# TLC4LEDShield.net
KiCad netlist of a schematic drawn in EAGLE
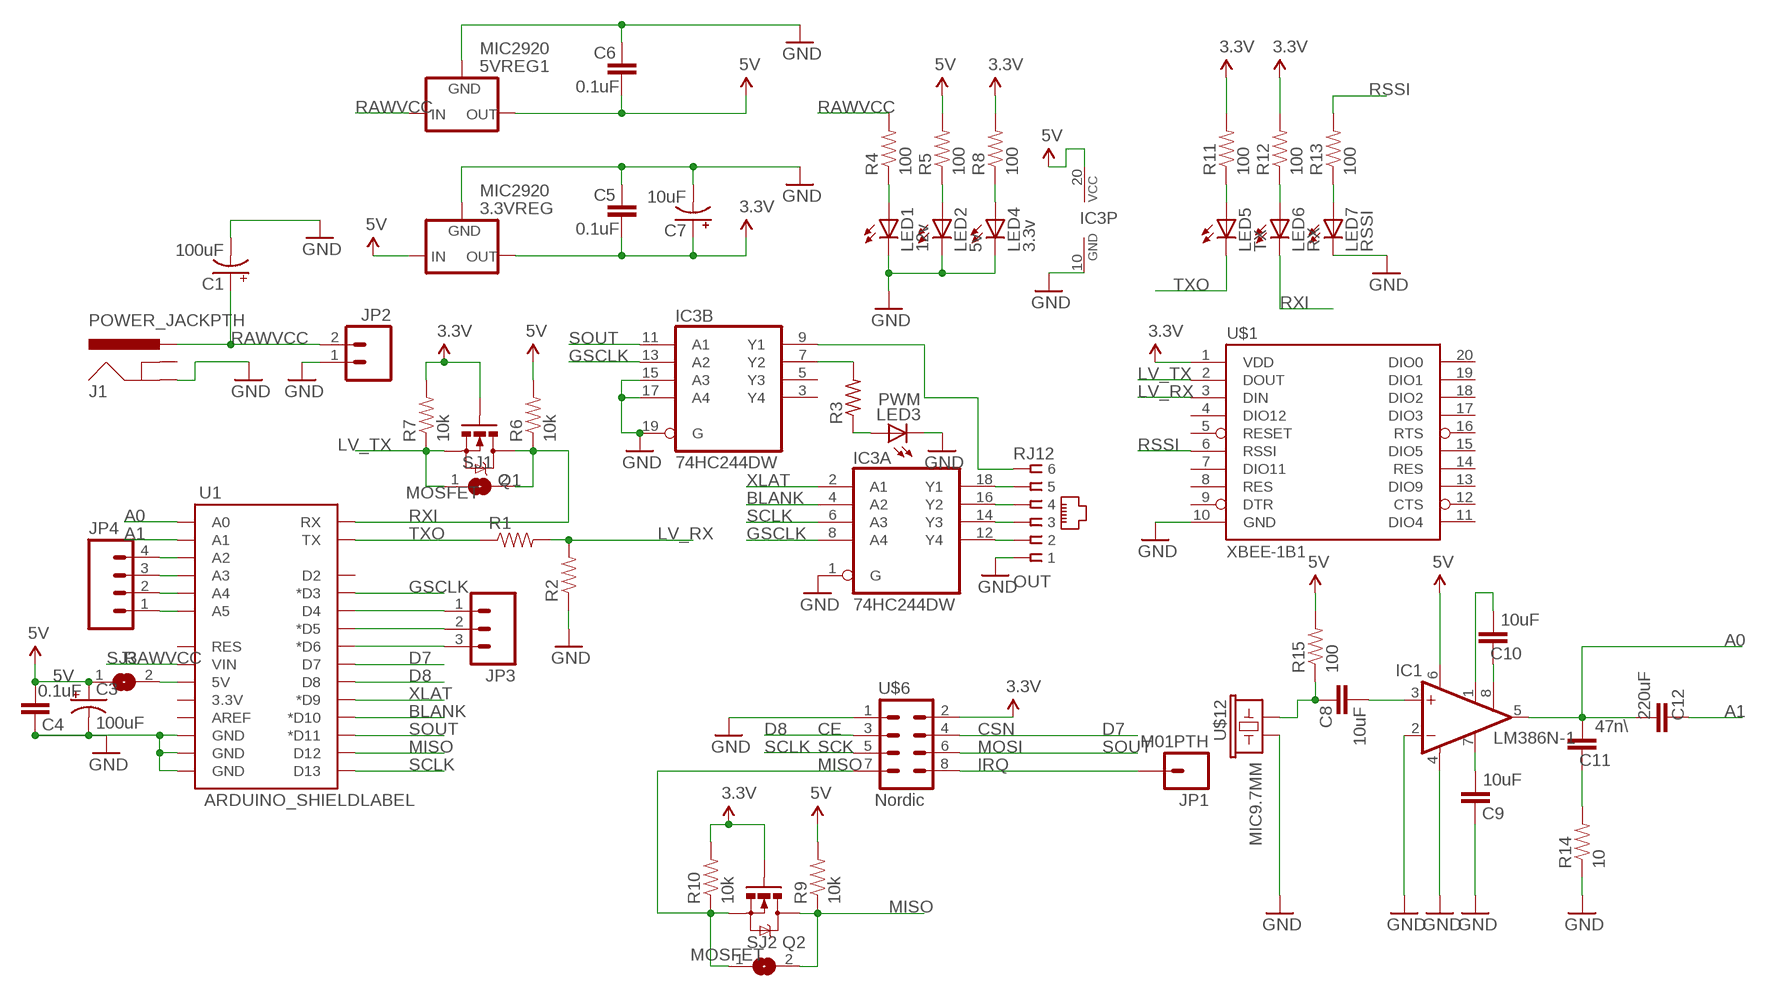
[diagram p0: schematic, sheet 1]

(export (version "E")
  (design (tool "Eeschema 10.0.6"))
  (components
    (comp (ref "3.3VREG")
      (value "MIC2920")
      (footprint "eagle-import:SOT223")
      (libsource (lib "eagle-import") (part "V_REG_MIC2920"))
    )
    (comp (ref "5VREG1")
      (value "MIC2920")
      (footprint "eagle-import:SOT223")
      (libsource (lib "eagle-import") (part "V_REG_MIC2920"))
    )
    (comp (ref "C1")
      (value "100uF")
      (footprint "eagle-import:PANASONIC_D")
      (libsource (lib "eagle-import") (part "CAP_POLD"))
    )
    (comp (ref "C3")
      (value "100uF")
      (footprint "eagle-import:PANASONIC_D")
      (libsource (lib "eagle-import") (part "CAP_POLD"))
    )
    (comp (ref "C4")
      (value "0.1uF")
      (footprint "eagle-import:0805")
      (libsource (lib "eagle-import") (part "CAP0805"))
    )
    (comp (ref "C5")
      (value "0.1uF")
      (footprint "eagle-import:0805")
      (libsource (lib "eagle-import") (part "CAP0805"))
    )
    (comp (ref "C6")
      (value "0.1uF")
      (footprint "eagle-import:0805")
      (libsource (lib "eagle-import") (part "CAP0805"))
    )
    (comp (ref "C7")
      (value "10uF")
      (footprint "eagle-import:EIA3216")
      (libsource (lib "eagle-import") (part "CAP_POL1206"))
    )
    (comp (ref "C8")
      (value "10uF")
      (footprint "eagle-import:0805")
      (libsource (lib "eagle-import") (part "CAP0805"))
    )
    (comp (ref "C9")
      (value "10uF")
      (footprint "eagle-import:0805")
      (libsource (lib "eagle-import") (part "CAP0805"))
    )
    (comp (ref "C10")
      (value "10uF")
      (footprint "eagle-import:0805")
      (libsource (lib "eagle-import") (part "CAP0805"))
    )
    (comp (ref "C11")
      (value "47n\\")
      (footprint "eagle-import:0805")
      (libsource (lib "eagle-import") (part "CAP0805"))
    )
    (comp (ref "C12")
      (value "220uF")
      (footprint "eagle-import:0805")
      (libsource (lib "eagle-import") (part "CAP0805"))
    )
    (comp (ref "IC1")
      (value "LM386N-1")
      (footprint "eagle-import:DIL08")
      (libsource (lib "eagle-import") (part "LM386?-N1"))
    )
    (comp (ref "IC3")
      (value "74HC244DW")
      (footprint "eagle-import:SO20W")
      (libsource (lib "eagle-import") (part "74244DWHC"))
    )
    (comp (ref "J1")
      (value "POWER_JACKPTH")
      (footprint "eagle-import:POWER_JACK_PTH")
      (libsource (lib "eagle-import") (part "POWER_JACKPTH"))
    )
    (comp (ref "JP1")
      (value "M01PTH")
      (footprint "eagle-import:1X01")
      (libsource (lib "eagle-import") (part "M01PTH"))
    )
    (comp (ref "JP2")
      (value "M025MM")
      (footprint "eagle-import:SCREWTERMINAL-5MM-2")
      (libsource (lib "eagle-import") (part "M025MM"))
    )
    (comp (ref "JP3")
      (value "M03PTH")
      (footprint "eagle-import:1X03")
      (libsource (lib "eagle-import") (part "M03PTH"))
    )
    (comp (ref "JP4")
      (value "M04PTH")
      (footprint "eagle-import:1X04")
      (libsource (lib "eagle-import") (part "M04PTH"))
    )
    (comp (ref "LED1")
      (value "12v")
      (footprint "eagle-import:CHIPLED_0805")
      (libsource (lib "eagle-import") (part "LEDCHIPLED_0805"))
    )
    (comp (ref "LED2")
      (value "5v")
      (footprint "eagle-import:CHIPLED_0805")
      (libsource (lib "eagle-import") (part "LEDCHIPLED_0805"))
    )
    (comp (ref "LED3")
      (value "PWM")
      (footprint "eagle-import:CHIPLED_0805")
      (libsource (lib "eagle-import") (part "LEDCHIPLED_0805"))
    )
    (comp (ref "LED4")
      (value "3.3v")
      (footprint "eagle-import:CHIPLED_0805")
      (libsource (lib "eagle-import") (part "LEDCHIPLED_0805"))
    )
    (comp (ref "LED5")
      (value "TX")
      (footprint "eagle-import:CHIPLED_0805")
      (libsource (lib "eagle-import") (part "LEDCHIPLED_0805"))
    )
    (comp (ref "LED6")
      (value "RX")
      (footprint "eagle-import:CHIPLED_0805")
      (libsource (lib "eagle-import") (part "LEDCHIPLED_0805"))
    )
    (comp (ref "LED7")
      (value "RSSI")
      (footprint "eagle-import:CHIPLED_0805")
      (libsource (lib "eagle-import") (part "LEDCHIPLED_0805"))
    )
    (comp (ref "OUT")
      (value "RJ12")
      (footprint "eagle-import:RJ11-NO_SHIELD")
      (fields
        (field (name "MF") "TYCO ELECTRONICS")
        (field (name "MPN") "RJ11-6L-B")
        (field (name "MF_1") "TYCO ELECTRONICS")
        (field (name "MPN_1") "RJ11-6L-B")
        (field (name "OC_FARNELL") "unknown")
        (field (name "OC_NEWARK") "52K3613")
      )
      (libsource (lib "eagle-import") (part "RJ11-6L-B"))
    )
    (comp (ref "Q1")
      (value "MOSFET")
      (footprint "eagle-import:SOT23-3")
      (libsource (lib "eagle-import") (part "MOSFET-NCHANNELSMD"))
    )
    (comp (ref "Q2")
      (value "MOSFET")
      (footprint "eagle-import:SOT23-3")
      (libsource (lib "eagle-import") (part "MOSFET-NCHANNELSMD"))
    )
    (comp (ref "R1")
      (value "RESISTOR0805-RES")
      (footprint "eagle-import:0805")
      (libsource (lib "eagle-import") (part "RESISTOR0805-RES"))
    )
    (comp (ref "R2")
      (value "RESISTOR0805-RES")
      (footprint "eagle-import:0805")
      (libsource (lib "eagle-import") (part "RESISTOR0805-RES"))
    )
    (comp (ref "R3")
      (value "R-US_R0805")
      (footprint "eagle-import:R0805")
      (libsource (lib "eagle-import") (part "R-US_R0805"))
    )
    (comp (ref "R4")
      (value "100")
      (footprint "eagle-import:0805")
      (libsource (lib "eagle-import") (part "RESISTOR0805-RES"))
    )
    (comp (ref "R5")
      (value "100")
      (footprint "eagle-import:0805")
      (libsource (lib "eagle-import") (part "RESISTOR0805-RES"))
    )
    (comp (ref "R6")
      (value "10k")
      (footprint "eagle-import:0805")
      (libsource (lib "eagle-import") (part "RESISTOR0805-RES"))
    )
    (comp (ref "R7")
      (value "10k")
      (footprint "eagle-import:0805")
      (libsource (lib "eagle-import") (part "RESISTOR0805-RES"))
    )
    (comp (ref "R8")
      (value "100")
      (footprint "eagle-import:0805")
      (libsource (lib "eagle-import") (part "RESISTOR0805-RES"))
    )
    (comp (ref "R9")
      (value "10k")
      (footprint "eagle-import:0805")
      (libsource (lib "eagle-import") (part "RESISTOR0805-RES"))
    )
    (comp (ref "R10")
      (value "10k")
      (footprint "eagle-import:0805")
      (libsource (lib "eagle-import") (part "RESISTOR0805-RES"))
    )
    (comp (ref "R11")
      (value "100")
      (footprint "eagle-import:0805")
      (libsource (lib "eagle-import") (part "RESISTOR0805-RES"))
    )
    (comp (ref "R12")
      (value "100")
      (footprint "eagle-import:0805")
      (libsource (lib "eagle-import") (part "RESISTOR0805-RES"))
    )
    (comp (ref "R13")
      (value "100")
      (footprint "eagle-import:0805")
      (libsource (lib "eagle-import") (part "RESISTOR0805-RES"))
    )
    (comp (ref "R14")
      (value "10")
      (footprint "eagle-import:0805")
      (libsource (lib "eagle-import") (part "RESISTOR0805-RES"))
    )
    (comp (ref "R15")
      (value "100")
      (footprint "eagle-import:0805")
      (libsource (lib "eagle-import") (part "RESISTOR0805-RES"))
    )
    (comp (ref "SJ1") (value "SJ") (footprint "eagle-import:SJ") (libsource (lib "eagle-import") (part "SJ")))
    (comp (ref "SJ2") (value "SJ") (footprint "eagle-import:SJ") (libsource (lib "eagle-import") (part "SJ")))
    (comp (ref "SJ3") (value "SJ") (footprint "eagle-import:SJ") (libsource (lib "eagle-import") (part "SJ")))
    (comp (ref "U$1")
      (value "XBEE-1B1")
      (footprint "eagle-import:XBEE-1")
      (libsource (lib "eagle-import") (part "XBEE-1B1"))
    )
    (comp (ref "U$6")
      (value "Nordic")
      (footprint "eagle-import:2X4")
      (libsource (lib "eagle-import") (part "M04X2"))
    )
    (comp (ref "U$12")
      (value "MIC9.7MM")
      (footprint "eagle-import:MIC-9.7MM")
      (libsource (lib "eagle-import") (part "MIC9.7MM"))
    )
    (comp (ref "U1")
      (value "ARDUINO_SHIELDLABEL")
      (footprint "eagle-import:DUEMILANOVE_SHIELD")
      (libsource (lib "eagle-import") (part "ARDUINO_SHIELDLABEL"))
    )
  )
  (nets
    (net (code "1") (name "/A0") (class "Default")
      (node (ref "C11") (pin "1") (pinfunction "1_1") (pintype "passive"))
      (node (ref "C12") (pin "1") (pinfunction "1_1") (pintype "passive"))
      (node (ref "IC1") (pin "5") (pinfunction "OUT_5") (pintype "output"))
      (node (ref "U1") (pin "A0") (pinfunction "A0_A0") (pintype "bidirectional"))
    )
    (net (code "2") (name "/A1") (class "Default")
      (node (ref "C12") (pin "2") (pinfunction "2_2") (pintype "passive"))
      (node (ref "U1") (pin "A1") (pinfunction "A1_A1") (pintype "bidirectional"))
    )
    (net (code "3") (name "/BLANK") (class "Default")
      (node (ref "IC3") (pin "4") (pinfunction "A2_4") (pintype "input"))
      (node (ref "U1") (pin "D10") (pinfunction "*D10_D10") (pintype "bidirectional"))
    )
    (net (code "4") (name "/D7") (class "Default")
      (node (ref "U$6") (pin "4") (pinfunction "4_4") (pintype "passive"))
      (node (ref "U1") (pin "D7") (pinfunction "D7_D7") (pintype "bidirectional"))
    )
    (net (code "5") (name "/D8") (class "Default")
      (node (ref "U$6") (pin "3") (pinfunction "3_3") (pintype "passive"))
      (node (ref "U1") (pin "D8") (pinfunction "D8_D8") (pintype "bidirectional"))
    )
    (net (code "6") (name "/GSCLK") (class "Default")
      (node (ref "IC3") (pin "13") (pinfunction "A2_13") (pintype "input"))
      (node (ref "IC3") (pin "8") (pinfunction "A4_8") (pintype "input"))
      (node (ref "U1") (pin "D3") (pinfunction "*D3_D3") (pintype "bidirectional"))
    )
    (net (code "7") (name "/LV_RX") (class "Default")
      (node (ref "R1") (pin "2") (pinfunction "2_2") (pintype "passive"))
      (node (ref "R2") (pin "2") (pinfunction "2_2") (pintype "passive"))
      (node (ref "U$1") (pin "3") (pinfunction "DIN_3") (pintype "input"))
    )
    (net (code "8") (name "/LV_TX") (class "Default")
      (node (ref "Q1") (pin "2") (pinfunction "S_2") (pintype "passive"))
      (node (ref "R7") (pin "1") (pinfunction "1_1") (pintype "passive"))
      (node (ref "SJ1") (pin "1") (pinfunction "1_1") (pintype "passive"))
      (node (ref "U$1") (pin "2") (pinfunction "DOUT_2") (pintype "output"))
    )
    (net (code "9") (name "/MISO") (class "Default")
      (node (ref "Q2") (pin "3") (pinfunction "D_3") (pintype "passive"))
      (node (ref "R9") (pin "1") (pinfunction "1_1") (pintype "passive"))
      (node (ref "SJ2") (pin "2") (pinfunction "2_2") (pintype "passive"))
      (node (ref "U1") (pin "D12") (pinfunction "D12_D12") (pintype "bidirectional"))
    )
    (net (code "10") (name "/RAWVCC") (class "Default")
      (node (ref "5VREG1") (pin "1") (pinfunction "IN_1") (pintype "input"))
      (node (ref "C1") (pin "+") (pinfunction "+_+") (pintype "passive"))
      (node (ref "J1") (pin "PWR") (pinfunction "PWR_PWR") (pintype "bidirectional"))
      (node (ref "JP2") (pin "2") (pinfunction "2_2") (pintype "passive"))
      (node (ref "R4") (pin "2") (pinfunction "2_2") (pintype "passive"))
      (node (ref "U1") (pin "VIN") (pinfunction "VIN_VIN") (pintype "bidirectional"))
    )
    (net (code "11") (name "/RSSI") (class "Default")
      (node (ref "R13") (pin "2") (pinfunction "2_2") (pintype "passive"))
      (node (ref "U$1") (pin "6") (pinfunction "RSSI_6") (pintype "bidirectional"))
    )
    (net (code "12") (name "/RXI") (class "Default")
      (node (ref "LED6") (pin "C") (pinfunction "C_C") (pintype "passive"))
      (node (ref "Q1") (pin "3") (pinfunction "D_3") (pintype "passive"))
      (node (ref "R6") (pin "1") (pinfunction "1_1") (pintype "passive"))
      (node (ref "SJ1") (pin "2") (pinfunction "2_2") (pintype "passive"))
      (node (ref "U1") (pin "RX") (pinfunction "RX_RX") (pintype "bidirectional"))
    )
    (net (code "13") (name "/SCLK") (class "Default")
      (node (ref "IC3") (pin "6") (pinfunction "A3_6") (pintype "input"))
      (node (ref "U$6") (pin "5") (pinfunction "5_5") (pintype "passive"))
      (node (ref "U1") (pin "D13") (pinfunction "D13_D13") (pintype "bidirectional"))
    )
    (net (code "14") (name "/SOUT") (class "Default")
      (node (ref "IC3") (pin "11") (pinfunction "A1_11") (pintype "input"))
      (node (ref "U$6") (pin "6") (pinfunction "6_6") (pintype "passive"))
      (node (ref "U1") (pin "D11") (pinfunction "*D11_D11") (pintype "bidirectional"))
    )
    (net (code "15") (name "/TXO") (class "Default")
      (node (ref "LED5") (pin "C") (pinfunction "C_C") (pintype "passive"))
      (node (ref "R1") (pin "1") (pinfunction "1_1") (pintype "passive"))
      (node (ref "U1") (pin "TX") (pinfunction "TX_TX") (pintype "bidirectional"))
    )
    (net (code "16") (name "/XLAT") (class "Default")
      (node (ref "IC3") (pin "2") (pinfunction "A1_2") (pintype "input"))
      (node (ref "U1") (pin "D9") (pinfunction "*D9_D9") (pintype "bidirectional"))
    )
    (net (code "17") (name "3.3V") (class "Default")
      (node (ref "3.3VREG") (pin "3") (pinfunction "OUT_3") (pintype "output"))
      (node (ref "C5") (pin "1") (pinfunction "1_1") (pintype "passive"))
      (node (ref "C7") (pin "A") (pinfunction "+_A") (pintype "passive"))
      (node (ref "Q1") (pin "1") (pinfunction "G_1") (pintype "passive"))
      (node (ref "Q2") (pin "1") (pinfunction "G_1") (pintype "passive"))
      (node (ref "R10") (pin "2") (pinfunction "2_2") (pintype "passive"))
      (node (ref "R11") (pin "2") (pinfunction "2_2") (pintype "passive"))
      (node (ref "R12") (pin "2") (pinfunction "2_2") (pintype "passive"))
      (node (ref "R7") (pin "2") (pinfunction "2_2") (pintype "passive"))
      (node (ref "R8") (pin "2") (pinfunction "2_2") (pintype "passive"))
      (node (ref "U$1") (pin "1") (pinfunction "VDD_1") (pintype "power_in"))
      (node (ref "U$6") (pin "2") (pinfunction "2_2") (pintype "passive"))
    )
    (net (code "18") (name "5V") (class "Default")
      (node (ref "3.3VREG") (pin "1") (pinfunction "IN_1") (pintype "input"))
      (node (ref "5VREG1") (pin "3") (pinfunction "OUT_3") (pintype "output"))
      (node (ref "C3") (pin "+") (pinfunction "+_+") (pintype "passive"))
      (node (ref "C4") (pin "1") (pinfunction "1_1") (pintype "passive"))
      (node (ref "C6") (pin "1") (pinfunction "1_1") (pintype "passive"))
      (node (ref "IC1") (pin "6") (pinfunction "VS_6") (pintype "power_in"))
      (node (ref "IC3") (pin "20") (pinfunction "VCC_20") (pintype "power_in"))
      (node (ref "R15") (pin "2") (pinfunction "2_2") (pintype "passive"))
      (node (ref "R5") (pin "2") (pinfunction "2_2") (pintype "passive"))
      (node (ref "R6") (pin "2") (pinfunction "2_2") (pintype "passive"))
      (node (ref "R9") (pin "2") (pinfunction "2_2") (pintype "passive"))
      (node (ref "SJ3") (pin "1") (pinfunction "1_1") (pintype "passive"))
    )
    (net (code "19") (name "GND") (class "Default")
      (node (ref "3.3VREG") (pin "2") (pinfunction "GND_2") (pintype "input"))
      (node (ref "5VREG1") (pin "2") (pinfunction "GND_2") (pintype "input"))
      (node (ref "C1") (pin "-") (pinfunction "-_-") (pintype "passive"))
      (node (ref "C3") (pin "-") (pinfunction "-_-") (pintype "passive"))
      (node (ref "C4") (pin "2") (pinfunction "2_2") (pintype "passive"))
      (node (ref "C5") (pin "2") (pinfunction "2_2") (pintype "passive"))
      (node (ref "C6") (pin "2") (pinfunction "2_2") (pintype "passive"))
      (node (ref "C7") (pin "C") (pinfunction "-_C") (pintype "passive"))
      (node (ref "C9") (pin "2") (pinfunction "2_2") (pintype "passive"))
      (node (ref "IC1") (pin "2") (pinfunction "-IN_2") (pintype "input"))
      (node (ref "IC1") (pin "4") (pinfunction "GND_4") (pintype "power_in"))
      (node (ref "IC3") (pin "1") (pinfunction "G_1") (pintype "input"))
      (node (ref "IC3") (pin "10") (pinfunction "GND_10") (pintype "power_in"))
      (node (ref "IC3") (pin "15") (pinfunction "A3_15") (pintype "input"))
      (node (ref "IC3") (pin "17") (pinfunction "A4_17") (pintype "input"))
      (node (ref "IC3") (pin "19") (pinfunction "G_19") (pintype "input"))
      (node (ref "J1") (pin "GND") (pinfunction "GND_GND") (pintype "bidirectional"))
      (node (ref "JP2") (pin "1") (pinfunction "1_1") (pintype "passive"))
      (node (ref "LED1") (pin "C") (pinfunction "C_C") (pintype "passive"))
      (node (ref "LED2") (pin "C") (pinfunction "C_C") (pintype "passive"))
      (node (ref "LED3") (pin "C") (pinfunction "C_C") (pintype "passive"))
      (node (ref "LED4") (pin "C") (pinfunction "C_C") (pintype "passive"))
      (node (ref "LED7") (pin "C") (pinfunction "C_C") (pintype "passive"))
      (node (ref "OUT") (pin "1") (pinfunction "1_1") (pintype "passive"))
      (node (ref "R14") (pin "1") (pinfunction "1_1") (pintype "passive"))
      (node (ref "R2") (pin "1") (pinfunction "1_1") (pintype "passive"))
      (node (ref "U$1") (pin "10") (pinfunction "GND_10") (pintype "power_in"))
      (node (ref "U$12") (pin "2") (pinfunction "2_2") (pintype "passive"))
      (node (ref "U$6") (pin "1") (pinfunction "1_1") (pintype "passive"))
      (node (ref "U1") (pin "GND@0") (pinfunction "GND_GND@0") (pintype "bidirectional"))
      (node (ref "U1") (pin "GND@1") (pinfunction "GND_GND@1") (pintype "bidirectional"))
      (node (ref "U1") (pin "GND@2") (pinfunction "GND_GND@2") (pintype "bidirectional"))
    )
    (net (code "20") (name "Net-(C8-Pad2)") (class "Default")
      (node (ref "C8") (pin "2") (pinfunction "2_2") (pintype "passive"))
      (node (ref "R15") (pin "1") (pinfunction "1_1") (pintype "passive"))
      (node (ref "U$12") (pin "1") (pinfunction "1_1") (pintype "passive"))
    )
    (net (code "21") (name "Net-(C10-Pad1)") (class "Default")
      (node (ref "C10") (pin "1") (pinfunction "1_1") (pintype "passive"))
      (node (ref "IC1") (pin "1") (pinfunction "GAIN_1") (pintype "passive"))
    )
    (net (code "22") (name "Net-(C10-Pad2)") (class "Default")
      (node (ref "C10") (pin "2") (pinfunction "2_2") (pintype "passive"))
      (node (ref "IC1") (pin "8") (pinfunction "GAIN_8") (pintype "passive"))
    )
    (net (code "23") (name "Net-(C11-Pad2)") (class "Default")
      (node (ref "C11") (pin "2") (pinfunction "2_2") (pintype "passive"))
      (node (ref "R14") (pin "2") (pinfunction "2_2") (pintype "passive"))
    )
    (net (code "24") (name "Net-(IC1-+IN)") (class "Default")
      (node (ref "C8") (pin "1") (pinfunction "1_1") (pintype "passive"))
      (node (ref "IC1") (pin "3") (pinfunction "+IN_3") (pintype "input"))
    )
    (net (code "25") (name "Net-(IC1-BYPASS)") (class "Default")
      (node (ref "C9") (pin "1") (pinfunction "1_1") (pintype "passive"))
      (node (ref "IC1") (pin "7") (pinfunction "BYPASS_7") (pintype "passive"))
    )
    (net (code "26") (name "Net-(IC3A-Y1)") (class "Default")
      (node (ref "IC3") (pin "18") (pinfunction "Y1_18") (pintype "tri_state"))
      (node (ref "OUT") (pin "5") (pinfunction "5_5") (pintype "passive"))
    )
    (net (code "27") (name "Net-(IC3A-Y2)") (class "Default")
      (node (ref "IC3") (pin "16") (pinfunction "Y2_16") (pintype "tri_state"))
      (node (ref "OUT") (pin "4") (pinfunction "4_4") (pintype "passive"))
    )
    (net (code "28") (name "Net-(IC3A-Y3)") (class "Default")
      (node (ref "IC3") (pin "14") (pinfunction "Y3_14") (pintype "tri_state"))
      (node (ref "OUT") (pin "3") (pinfunction "3_3") (pintype "passive"))
    )
    (net (code "29") (name "Net-(IC3A-Y4)") (class "Default")
      (node (ref "IC3") (pin "12") (pinfunction "Y4_12") (pintype "tri_state"))
      (node (ref "OUT") (pin "2") (pinfunction "2_2") (pintype "passive"))
    )
    (net (code "30") (name "Net-(IC3B-Y1)") (class "Default")
      (node (ref "IC3") (pin "9") (pinfunction "Y1_9") (pintype "tri_state"))
      (node (ref "OUT") (pin "6") (pinfunction "6_6") (pintype "passive"))
    )
    (net (code "31") (name "Net-(IC3B-Y2)") (class "Default")
      (node (ref "IC3") (pin "7") (pinfunction "Y2_7") (pintype "tri_state"))
      (node (ref "R3") (pin "2") (pinfunction "2_2") (pintype "passive"))
    )
    (net (code "32") (name "Net-(JP1-Pad1)") (class "Default")
      (node (ref "JP1") (pin "1") (pinfunction "1_1") (pintype "passive"))
      (node (ref "U$6") (pin "8") (pinfunction "8_8") (pintype "passive"))
    )
    (net (code "33") (name "Net-(JP3-Pad1)") (class "Default")
      (node (ref "JP3") (pin "1") (pinfunction "1_1") (pintype "passive"))
      (node (ref "U1") (pin "D4") (pinfunction "D4_D4") (pintype "bidirectional"))
    )
    (net (code "34") (name "Net-(JP4-Pad1)") (class "Default")
      (node (ref "JP4") (pin "1") (pinfunction "1_1") (pintype "passive"))
      (node (ref "U1") (pin "A5") (pinfunction "A5_A5") (pintype "bidirectional"))
    )
    (net (code "35") (name "Net-(JP4-Pad2)") (class "Default")
      (node (ref "JP4") (pin "2") (pinfunction "2_2") (pintype "passive"))
      (node (ref "U1") (pin "A4") (pinfunction "A4_A4") (pintype "bidirectional"))
    )
    (net (code "36") (name "Net-(JP4-Pad3)") (class "Default")
      (node (ref "JP4") (pin "3") (pinfunction "3_3") (pintype "passive"))
      (node (ref "U1") (pin "A3") (pinfunction "A3_A3") (pintype "bidirectional"))
    )
    (net (code "37") (name "Net-(JP4-Pad4)") (class "Default")
      (node (ref "JP4") (pin "4") (pinfunction "4_4") (pintype "passive"))
      (node (ref "U1") (pin "A2") (pinfunction "A2_A2") (pintype "bidirectional"))
    )
    (net (code "38") (name "Net-(LED1-PadA)") (class "Default")
      (node (ref "LED1") (pin "A") (pinfunction "A_A") (pintype "passive"))
      (node (ref "R4") (pin "1") (pinfunction "1_1") (pintype "passive"))
    )
    (net (code "39") (name "Net-(LED2-PadA)") (class "Default")
      (node (ref "LED2") (pin "A") (pinfunction "A_A") (pintype "passive"))
      (node (ref "R5") (pin "1") (pinfunction "1_1") (pintype "passive"))
    )
    (net (code "40") (name "Net-(LED3-PadA)") (class "Default")
      (node (ref "LED3") (pin "A") (pinfunction "A_A") (pintype "passive"))
      (node (ref "R3") (pin "1") (pinfunction "1_1") (pintype "passive"))
    )
    (net (code "41") (name "Net-(LED4-PadA)") (class "Default")
      (node (ref "LED4") (pin "A") (pinfunction "A_A") (pintype "passive"))
      (node (ref "R8") (pin "1") (pinfunction "1_1") (pintype "passive"))
    )
    (net (code "42") (name "Net-(LED5-PadA)") (class "Default")
      (node (ref "LED5") (pin "A") (pinfunction "A_A") (pintype "passive"))
      (node (ref "R11") (pin "1") (pinfunction "1_1") (pintype "passive"))
    )
    (net (code "43") (name "Net-(LED6-PadA)") (class "Default")
      (node (ref "LED6") (pin "A") (pinfunction "A_A") (pintype "passive"))
      (node (ref "R12") (pin "1") (pinfunction "1_1") (pintype "passive"))
    )
    (net (code "44") (name "Net-(LED7-PadA)") (class "Default")
      (node (ref "LED7") (pin "A") (pinfunction "A_A") (pintype "passive"))
      (node (ref "R13") (pin "1") (pinfunction "1_1") (pintype "passive"))
    )
    (net (code "45") (name "Net-(Q2-S)") (class "Default")
      (node (ref "Q2") (pin "2") (pinfunction "S_2") (pintype "passive"))
      (node (ref "R10") (pin "1") (pinfunction "1_1") (pintype "passive"))
      (node (ref "SJ2") (pin "1") (pinfunction "1_1") (pintype "passive"))
      (node (ref "U$6") (pin "7") (pinfunction "7_7") (pintype "passive"))
    )
    (net (code "46") (name "Net-(SJ3-Pad2)") (class "Default")
      (node (ref "SJ3") (pin "2") (pinfunction "2_2") (pintype "passive"))
      (node (ref "U1") (pin "5V") (pinfunction "5V_5V") (pintype "bidirectional"))
    )
    (net (code "47") (name "Net-(U1-*D5)") (class "Default")
      (node (ref "JP3") (pin "2") (pinfunction "2_2") (pintype "passive"))
      (node (ref "U1") (pin "D5") (pinfunction "*D5_D5") (pintype "bidirectional"))
    )
    (net (code "48") (name "Net-(U1-*D6)") (class "Default")
      (node (ref "JP3") (pin "3") (pinfunction "3_3") (pintype "passive"))
      (node (ref "U1") (pin "D6") (pinfunction "*D6_D6") (pintype "bidirectional"))
    )
    (net (code "49") (name "unconnected-(IC3B-Y3-Pad5)") (class "Default")
      (node (ref "IC3") (pin "5") (pinfunction "Y3_5") (pintype "tri_state"))
    )
    (net (code "50") (name "unconnected-(IC3B-Y4-Pad3)") (class "Default")
      (node (ref "IC3") (pin "3") (pinfunction "Y4_3") (pintype "tri_state"))
    )
    (net (code "51") (name "unconnected-(J1-PadGNDBREAK)") (class "Default")
      (node (ref "J1") (pin "GNDBREAK") (pinfunction "GNDBREAK_GNDBREAK") (pintype "bidirectional"))
    )
    (net (code "52") (name "unconnected-(U$1-CTS-Pad12)") (class "Default")
      (node (ref "U$1") (pin "12") (pinfunction "CTS_12") (pintype "output"))
    )
    (net (code "53") (name "unconnected-(U$1-DIO0-Pad20)") (class "Default")
      (node (ref "U$1") (pin "20") (pinfunction "DIO0_20") (pintype "bidirectional"))
    )
    (net (code "54") (name "unconnected-(U$1-DIO1-Pad19)") (class "Default")
      (node (ref "U$1") (pin "19") (pinfunction "DIO1_19") (pintype "bidirectional"))
    )
    (net (code "55") (name "unconnected-(U$1-DIO2-Pad18)") (class "Default")
      (node (ref "U$1") (pin "18") (pinfunction "DIO2_18") (pintype "bidirectional"))
    )
    (net (code "56") (name "unconnected-(U$1-DIO3-Pad17)") (class "Default")
      (node (ref "U$1") (pin "17") (pinfunction "DIO3_17") (pintype "bidirectional"))
    )
    (net (code "57") (name "unconnected-(U$1-DIO4-Pad11)") (class "Default")
      (node (ref "U$1") (pin "11") (pinfunction "DIO4_11") (pintype "bidirectional"))
    )
    (net (code "58") (name "unconnected-(U$1-DIO5-Pad15)") (class "Default")
      (node (ref "U$1") (pin "15") (pinfunction "DIO5_15") (pintype "bidirectional"))
    )
    (net (code "59") (name "unconnected-(U$1-DIO9-Pad13)") (class "Default")
      (node (ref "U$1") (pin "13") (pinfunction "DIO9_13") (pintype "bidirectional"))
    )
    (net (code "60") (name "unconnected-(U$1-DIO11-Pad7)") (class "Default")
      (node (ref "U$1") (pin "7") (pinfunction "DIO11_7") (pintype "bidirectional"))
    )
    (net (code "61") (name "unconnected-(U$1-DIO12-Pad4)") (class "Default")
      (node (ref "U$1") (pin "4") (pinfunction "DIO12_4") (pintype "bidirectional"))
    )
    (net (code "62") (name "unconnected-(U$1-DTR-Pad9)") (class "Default")
      (node (ref "U$1") (pin "9") (pinfunction "DTR_9") (pintype "bidirectional"))
    )
    (net (code "63") (name "unconnected-(U$1-RES-Pad8)") (class "Default")
      (node (ref "U$1") (pin "8") (pinfunction "RES_8") (pintype "bidirectional"))
    )
    (net (code "64") (name "unconnected-(U$1-RES-Pad14)") (class "Default")
      (node (ref "U$1") (pin "14") (pinfunction "RES_14") (pintype "bidirectional"))
    )
    (net (code "65") (name "unconnected-(U$1-RESET-Pad5)") (class "Default")
      (node (ref "U$1") (pin "5") (pinfunction "RESET_5") (pintype "input"))
    )
    (net (code "66") (name "unconnected-(U$1-RTS-Pad16)") (class "Default")
      (node (ref "U$1") (pin "16") (pinfunction "RTS_16") (pintype "input"))
    )
    (net (code "67") (name "unconnected-(U1-Pad3.3V)") (class "Default")
      (node (ref "U1") (pin "3.3V") (pinfunction "3.3V_3.3V") (pintype "bidirectional"))
    )
    (net (code "68") (name "unconnected-(U1-PadAREF)") (class "Default")
      (node (ref "U1") (pin "AREF") (pinfunction "AREF_AREF") (pintype "bidirectional"))
    )
    (net (code "69") (name "unconnected-(U1-PadD2)") (class "Default")
      (node (ref "U1") (pin "D2") (pinfunction "D2_D2") (pintype "bidirectional"))
    )
    (net (code "70") (name "unconnected-(U1-PadRES)") (class "Default")
      (node (ref "U1") (pin "RES") (pinfunction "RES_RES") (pintype "bidirectional"))
    )
  )
)
